# SCH_Instruction_Register_2021-10-21.net
KiCad netlist of a schematic drawn in EasyEDA
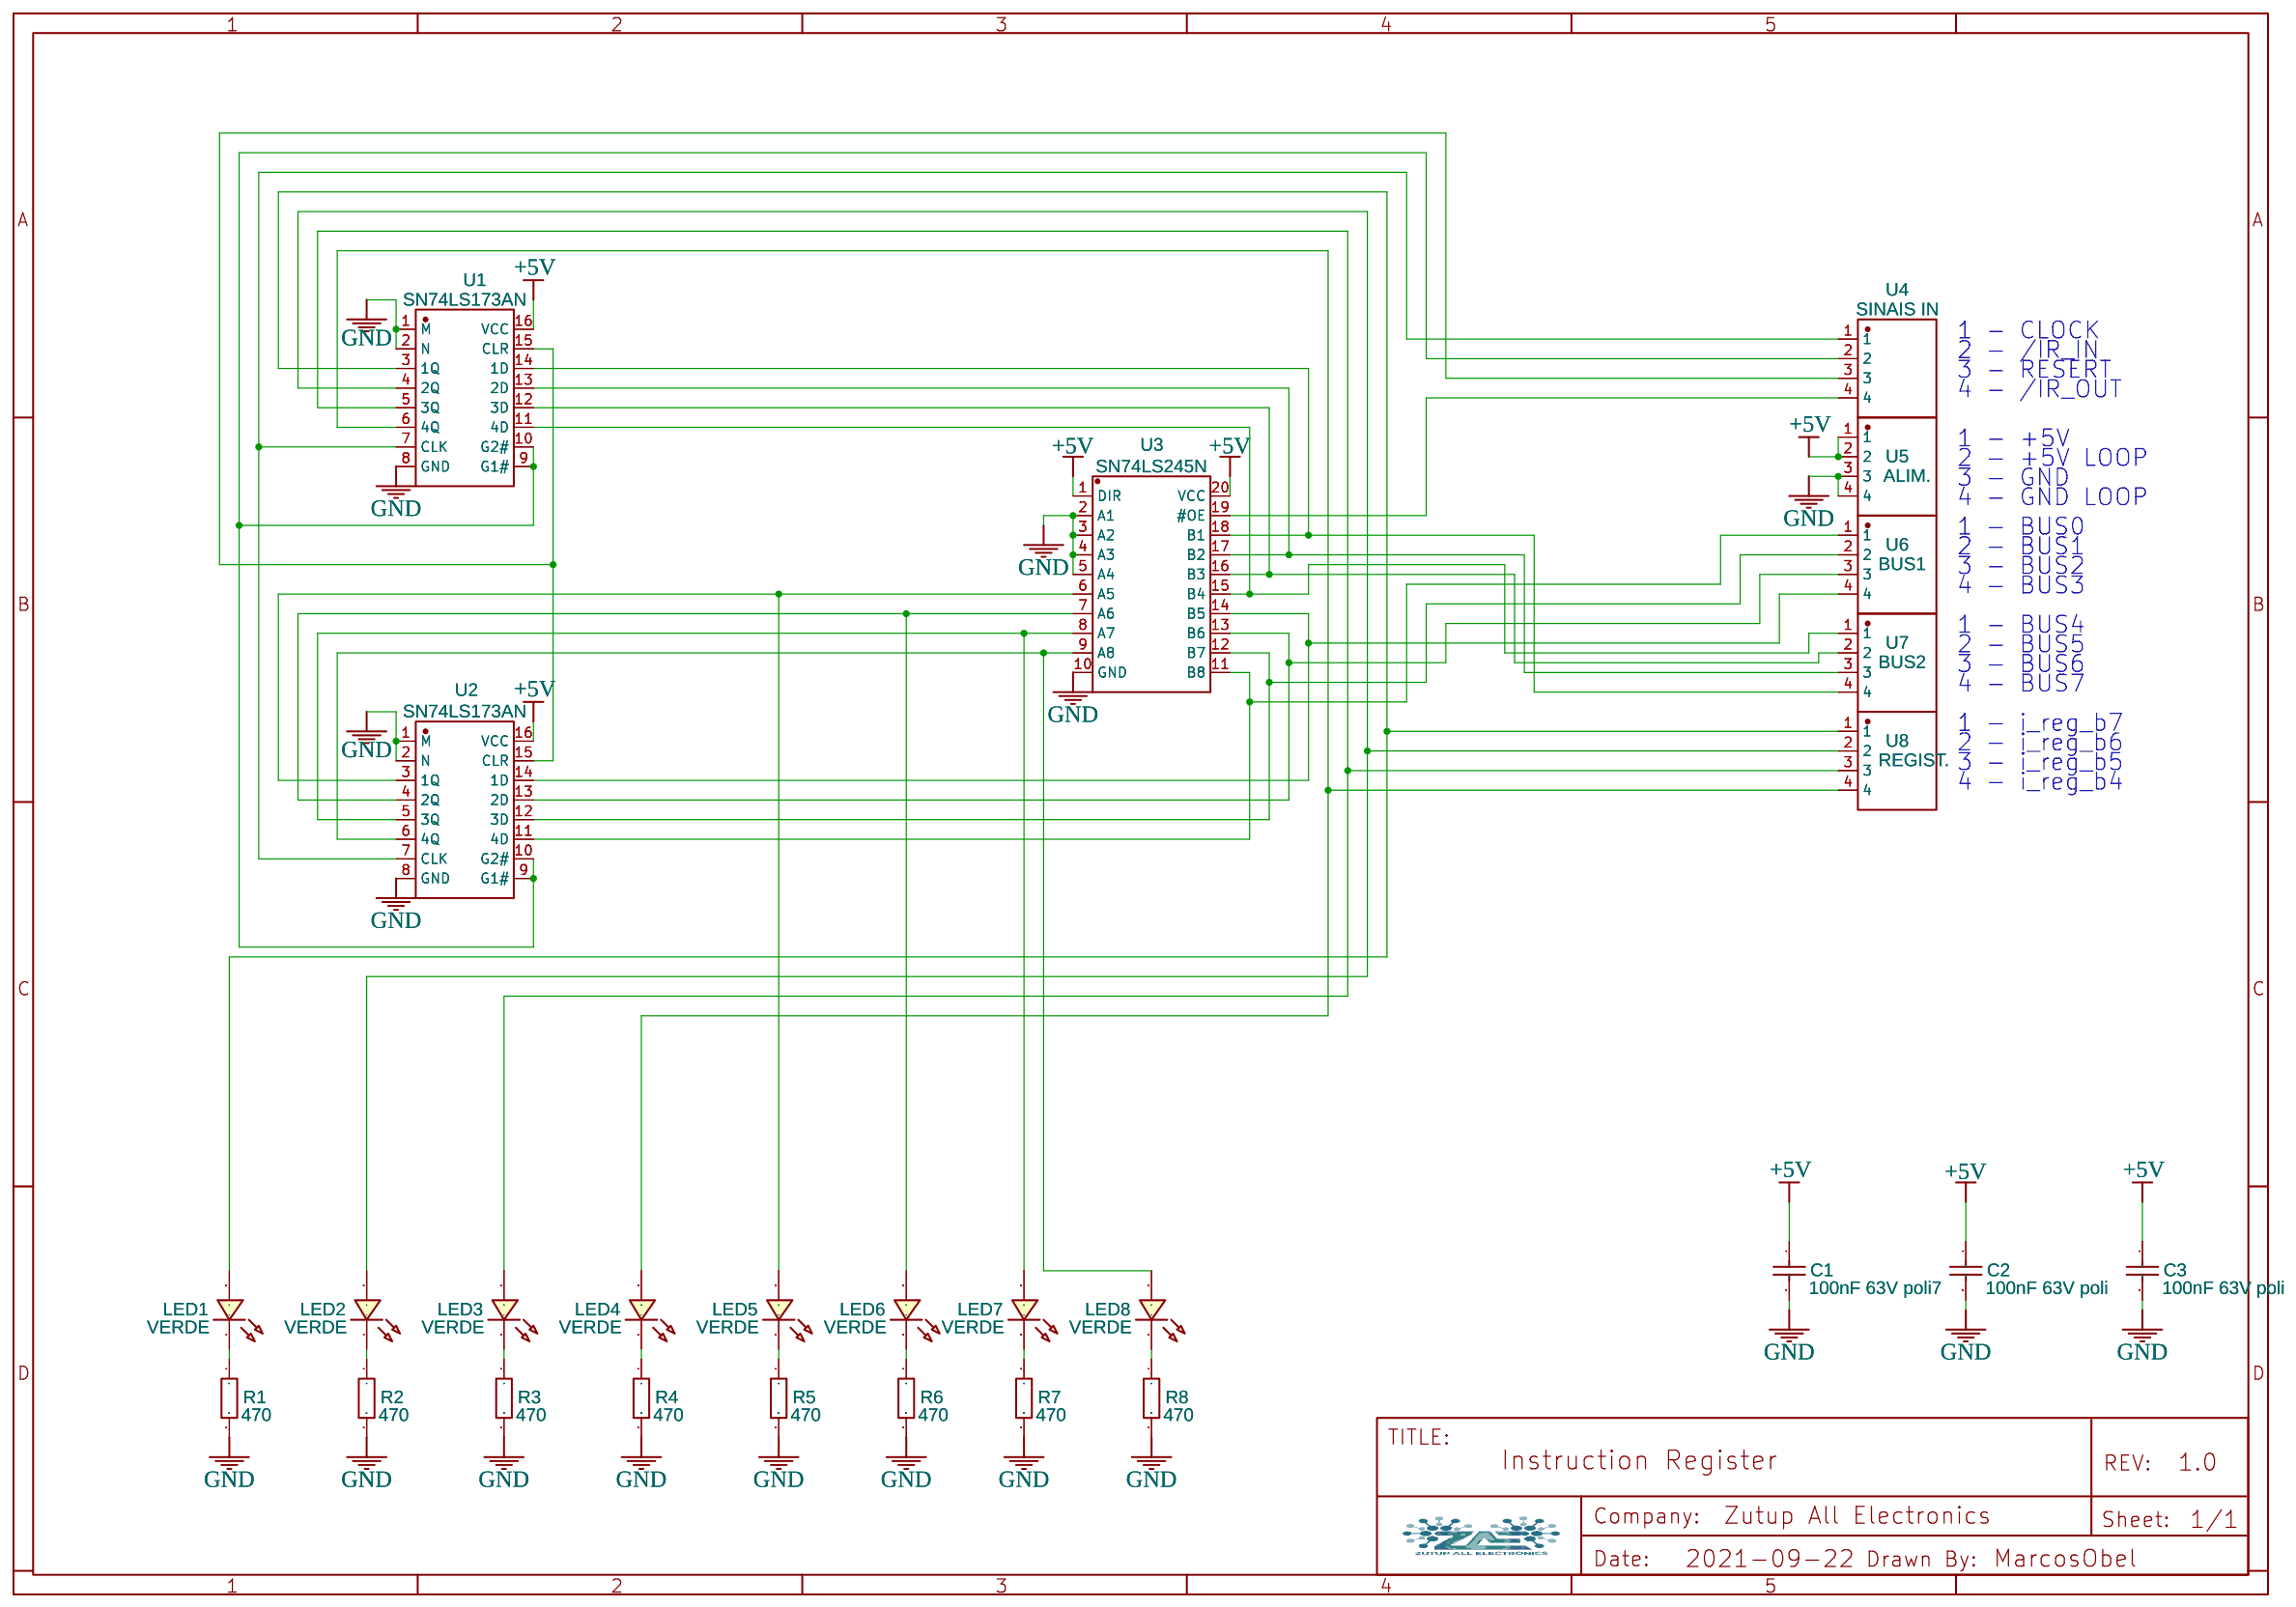
[diagram p0: schematic sheet]

(export (version "E")
  (design (tool "Eeschema 10.0.6"))
  (components
    (comp (ref "C1")
      (value "100nF 63V poli7")
      (fields
        (field (name "BOM_Manufacturer Part") "SR305C105KAR")
        (field (name "BOM_Supplier Part") "C444741")
      )
      (libsource (lib "") (part "SR305C105KAR"))
    )
    (comp (ref "C2")
      (value "100nF 63V poli")
      (fields
        (field (name "BOM_Manufacturer Part") "SR305C105KAR")
        (field (name "BOM_Supplier Part") "C444741")
      )
      (libsource (lib "") (part "SR305C105KAR"))
    )
    (comp (ref "C3")
      (value "100nF 63V poli")
      (fields
        (field (name "BOM_Manufacturer Part") "SR305C105KAR")
        (field (name "BOM_Supplier Part") "C444741")
      )
      (libsource (lib "") (part "SR305C105KAR"))
    )
    (comp (ref "LED1")
      (value "VERDE")
      (fields (field (name "BOM_Manufacturer Part") "264-7GD") (field (name "BOM_Supplier Part") "C605465"))
      (libsource (lib "") (part "264-7GD"))
    )
    (comp (ref "LED2")
      (value "VERDE")
      (fields (field (name "BOM_Manufacturer Part") "264-7GD") (field (name "BOM_Supplier Part") "C605465"))
      (libsource (lib "") (part "264-7GD"))
    )
    (comp (ref "LED3")
      (value "VERDE")
      (fields (field (name "BOM_Manufacturer Part") "264-7GD") (field (name "BOM_Supplier Part") "C605465"))
      (libsource (lib "") (part "264-7GD"))
    )
    (comp (ref "LED4")
      (value "VERDE")
      (fields (field (name "BOM_Manufacturer Part") "264-7GD") (field (name "BOM_Supplier Part") "C605465"))
      (libsource (lib "") (part "264-7GD"))
    )
    (comp (ref "LED5")
      (value "VERDE")
      (fields (field (name "BOM_Manufacturer Part") "264-7GD") (field (name "BOM_Supplier Part") "C605465"))
      (libsource (lib "") (part "264-7GD"))
    )
    (comp (ref "LED6")
      (value "VERDE")
      (fields (field (name "BOM_Manufacturer Part") "264-7GD") (field (name "BOM_Supplier Part") "C605465"))
      (libsource (lib "") (part "264-7GD"))
    )
    (comp (ref "LED7")
      (value "VERDE")
      (fields (field (name "BOM_Manufacturer Part") "264-7GD") (field (name "BOM_Supplier Part") "C605465"))
      (libsource (lib "") (part "264-7GD"))
    )
    (comp (ref "LED8")
      (value "VERDE")
      (fields (field (name "BOM_Manufacturer Part") "264-7GD") (field (name "BOM_Supplier Part") "C605465"))
      (libsource (lib "") (part "264-7GD"))
    )
    (comp (ref "R1")
      (value "470")
      (fields
        (field (name "BOM_Manufacturer Part") "CFR02SJ0823A10")
        (field (name "BOM_Supplier Part") "C69876")
      )
      (libsource (lib "") (part "CFR02SJ0823A10"))
    )
    (comp (ref "R2")
      (value "470")
      (fields
        (field (name "BOM_Manufacturer Part") "CFR02SJ0823A10")
        (field (name "BOM_Supplier Part") "C69876")
      )
      (libsource (lib "") (part "CFR02SJ0823A10"))
    )
    (comp (ref "R3")
      (value "470")
      (fields
        (field (name "BOM_Manufacturer Part") "CFR02SJ0823A10")
        (field (name "BOM_Supplier Part") "C69876")
      )
      (libsource (lib "") (part "CFR02SJ0823A10"))
    )
    (comp (ref "R4")
      (value "470")
      (fields
        (field (name "BOM_Manufacturer Part") "CFR02SJ0823A10")
        (field (name "BOM_Supplier Part") "C69876")
      )
      (libsource (lib "") (part "CFR02SJ0823A10"))
    )
    (comp (ref "R5")
      (value "470")
      (fields
        (field (name "BOM_Manufacturer Part") "CFR02SJ0823A10")
        (field (name "BOM_Supplier Part") "C69876")
      )
      (libsource (lib "") (part "CFR02SJ0823A10"))
    )
    (comp (ref "R6")
      (value "470")
      (fields
        (field (name "BOM_Manufacturer Part") "CFR02SJ0823A10")
        (field (name "BOM_Supplier Part") "C69876")
      )
      (libsource (lib "") (part "CFR02SJ0823A10"))
    )
    (comp (ref "R7")
      (value "470")
      (fields
        (field (name "BOM_Manufacturer Part") "CFR02SJ0823A10")
        (field (name "BOM_Supplier Part") "C69876")
      )
      (libsource (lib "") (part "CFR02SJ0823A10"))
    )
    (comp (ref "R8")
      (value "470")
      (fields
        (field (name "BOM_Manufacturer Part") "CFR02SJ0823A10")
        (field (name "BOM_Supplier Part") "C69876")
      )
      (libsource (lib "") (part "CFR02SJ0823A10"))
    )
    (comp (ref "U1")
      (value "SN74LS173AN")
      (fields (field (name "BOM_Supplier Part") "C1550125"))
      (libsource (lib "") (part "SN74LS173AN"))
    )
    (comp (ref "U2")
      (value "SN74LS173AN")
      (fields (field (name "BOM_Supplier Part") "C1550125"))
      (libsource (lib "") (part "SN74LS173AN"))
    )
    (comp (ref "U3")
      (value "SN74LS245N")
      (fields (field (name "BOM_Supplier Part") "C352966"))
      (libsource (lib "") (part "SN74LS245N"))
    )
    (comp (ref "U4")
      (value "SINAIS IN")
      (fields (field (name "BOM_Manufacturer Part") "171825-4") (field (name "BOM_Supplier Part") "C210162"))
      (libsource (lib "") (part "171825-4"))
    )
    (comp (ref "U5")
      (value "ALIM.")
      (fields (field (name "BOM_Manufacturer Part") "171825-4") (field (name "BOM_Supplier Part") "C210162"))
      (libsource (lib "") (part "171825-4"))
    )
    (comp (ref "U6")
      (value "BUS1")
      (fields (field (name "BOM_Manufacturer Part") "171825-4") (field (name "BOM_Supplier Part") "C210162"))
      (libsource (lib "") (part "171825-4"))
    )
    (comp (ref "U7")
      (value "BUS2")
      (fields (field (name "BOM_Manufacturer Part") "171825-4") (field (name "BOM_Supplier Part") "C210162"))
      (libsource (lib "") (part "171825-4"))
    )
    (comp (ref "U8")
      (value "REGIST.")
      (fields (field (name "BOM_Manufacturer Part") "171825-4") (field (name "BOM_Supplier Part") "C210162"))
      (libsource (lib "") (part "171825-4"))
    )
  )
  (nets
    (net (code "1") (name "+5V") (class "Default")
      (node (ref "C1") (pin "1") (pinfunction "1_1") (pintype "input"))
      (node (ref "C2") (pin "1") (pinfunction "1_1") (pintype "input"))
      (node (ref "C3") (pin "1") (pinfunction "1_1") (pintype "input"))
      (node (ref "U1") (pin "16") (pinfunction "VCC_16") (pintype "unspecified"))
      (node (ref "U2") (pin "16") (pinfunction "VCC_16") (pintype "unspecified"))
      (node (ref "U3") (pin "1") (pinfunction "DIR_1") (pintype "unspecified"))
      (node (ref "U3") (pin "20") (pinfunction "VCC_20") (pintype "unspecified"))
      (node (ref "U5") (pin "1") (pinfunction "1_1") (pintype "unspecified"))
      (node (ref "U5") (pin "2") (pinfunction "2_2") (pintype "unspecified"))
    )
    (net (code "2") (name "GND") (class "Default")
      (node (ref "C1") (pin "2") (pinfunction "2_2") (pintype "input"))
      (node (ref "C2") (pin "2") (pinfunction "2_2") (pintype "input"))
      (node (ref "C3") (pin "2") (pinfunction "2_2") (pintype "input"))
      (node (ref "R1") (pin "2") (pinfunction "2_2") (pintype "input"))
      (node (ref "R2") (pin "2") (pinfunction "2_2") (pintype "input"))
      (node (ref "R3") (pin "2") (pinfunction "2_2") (pintype "input"))
      (node (ref "R4") (pin "2") (pinfunction "2_2") (pintype "input"))
      (node (ref "R5") (pin "2") (pinfunction "2_2") (pintype "input"))
      (node (ref "R6") (pin "2") (pinfunction "2_2") (pintype "input"))
      (node (ref "R7") (pin "2") (pinfunction "2_2") (pintype "input"))
      (node (ref "R8") (pin "2") (pinfunction "2_2") (pintype "input"))
      (node (ref "U1") (pin "1") (pinfunction "M_1") (pintype "unspecified"))
      (node (ref "U1") (pin "2") (pinfunction "N_2") (pintype "unspecified"))
      (node (ref "U1") (pin "8") (pinfunction "GND_8") (pintype "unspecified"))
      (node (ref "U2") (pin "1") (pinfunction "M_1") (pintype "unspecified"))
      (node (ref "U2") (pin "2") (pinfunction "N_2") (pintype "unspecified"))
      (node (ref "U2") (pin "8") (pinfunction "GND_8") (pintype "unspecified"))
      (node (ref "U3") (pin "10") (pinfunction "GND_10") (pintype "unspecified"))
      (node (ref "U3") (pin "2") (pinfunction "A1_2") (pintype "unspecified"))
      (node (ref "U3") (pin "3") (pinfunction "A2_3") (pintype "unspecified"))
      (node (ref "U3") (pin "4") (pinfunction "A3_4") (pintype "unspecified"))
      (node (ref "U3") (pin "5") (pinfunction "A4_5") (pintype "unspecified"))
      (node (ref "U5") (pin "3") (pinfunction "3_3") (pintype "unspecified"))
      (node (ref "U5") (pin "4") (pinfunction "4_4") (pintype "unspecified"))
    )
    (net (code "3") (name "Net-(LED1-+)") (class "Default")
      (node (ref "LED1") (pin "2") (pinfunction "+_2") (pintype "unspecified"))
      (node (ref "U1") (pin "3") (pinfunction "1Q_3") (pintype "unspecified"))
      (node (ref "U8") (pin "1") (pinfunction "1_1") (pintype "unspecified"))
    )
    (net (code "4") (name "Net-(LED1--)") (class "Default")
      (node (ref "LED1") (pin "1") (pinfunction "-_1") (pintype "unspecified"))
      (node (ref "R1") (pin "1") (pinfunction "1_1") (pintype "input"))
    )
    (net (code "5") (name "Net-(LED2-+)") (class "Default")
      (node (ref "LED2") (pin "2") (pinfunction "+_2") (pintype "unspecified"))
      (node (ref "U1") (pin "4") (pinfunction "2Q_4") (pintype "unspecified"))
      (node (ref "U8") (pin "2") (pinfunction "2_2") (pintype "unspecified"))
    )
    (net (code "6") (name "Net-(LED2--)") (class "Default")
      (node (ref "LED2") (pin "1") (pinfunction "-_1") (pintype "unspecified"))
      (node (ref "R2") (pin "1") (pinfunction "1_1") (pintype "input"))
    )
    (net (code "7") (name "Net-(LED3-+)") (class "Default")
      (node (ref "LED3") (pin "2") (pinfunction "+_2") (pintype "unspecified"))
      (node (ref "U1") (pin "5") (pinfunction "3Q_5") (pintype "unspecified"))
      (node (ref "U8") (pin "3") (pinfunction "3_3") (pintype "unspecified"))
    )
    (net (code "8") (name "Net-(LED3--)") (class "Default")
      (node (ref "LED3") (pin "1") (pinfunction "-_1") (pintype "unspecified"))
      (node (ref "R3") (pin "1") (pinfunction "1_1") (pintype "input"))
    )
    (net (code "9") (name "Net-(LED4-+)") (class "Default")
      (node (ref "LED4") (pin "2") (pinfunction "+_2") (pintype "unspecified"))
      (node (ref "U1") (pin "6") (pinfunction "4Q_6") (pintype "unspecified"))
      (node (ref "U8") (pin "4") (pinfunction "4_4") (pintype "unspecified"))
    )
    (net (code "10") (name "Net-(LED4--)") (class "Default")
      (node (ref "LED4") (pin "1") (pinfunction "-_1") (pintype "unspecified"))
      (node (ref "R4") (pin "1") (pinfunction "1_1") (pintype "input"))
    )
    (net (code "11") (name "Net-(LED5-+)") (class "Default")
      (node (ref "LED5") (pin "2") (pinfunction "+_2") (pintype "unspecified"))
      (node (ref "U2") (pin "3") (pinfunction "1Q_3") (pintype "unspecified"))
      (node (ref "U3") (pin "6") (pinfunction "A5_6") (pintype "unspecified"))
    )
    (net (code "12") (name "Net-(LED5--)") (class "Default")
      (node (ref "LED5") (pin "1") (pinfunction "-_1") (pintype "unspecified"))
      (node (ref "R5") (pin "1") (pinfunction "1_1") (pintype "input"))
    )
    (net (code "13") (name "Net-(LED6-+)") (class "Default")
      (node (ref "LED6") (pin "2") (pinfunction "+_2") (pintype "unspecified"))
      (node (ref "U2") (pin "4") (pinfunction "2Q_4") (pintype "unspecified"))
      (node (ref "U3") (pin "7") (pinfunction "A6_7") (pintype "unspecified"))
    )
    (net (code "14") (name "Net-(LED6--)") (class "Default")
      (node (ref "LED6") (pin "1") (pinfunction "-_1") (pintype "unspecified"))
      (node (ref "R6") (pin "1") (pinfunction "1_1") (pintype "input"))
    )
    (net (code "15") (name "Net-(LED7-+)") (class "Default")
      (node (ref "LED7") (pin "2") (pinfunction "+_2") (pintype "unspecified"))
      (node (ref "U2") (pin "5") (pinfunction "3Q_5") (pintype "unspecified"))
      (node (ref "U3") (pin "8") (pinfunction "A7_8") (pintype "unspecified"))
    )
    (net (code "16") (name "Net-(LED7--)") (class "Default")
      (node (ref "LED7") (pin "1") (pinfunction "-_1") (pintype "unspecified"))
      (node (ref "R7") (pin "1") (pinfunction "1_1") (pintype "input"))
    )
    (net (code "17") (name "Net-(LED8-+)") (class "Default")
      (node (ref "LED8") (pin "2") (pinfunction "+_2") (pintype "unspecified"))
      (node (ref "U2") (pin "6") (pinfunction "4Q_6") (pintype "unspecified"))
      (node (ref "U3") (pin "9") (pinfunction "A8_9") (pintype "unspecified"))
    )
    (net (code "18") (name "Net-(LED8--)") (class "Default")
      (node (ref "LED8") (pin "1") (pinfunction "-_1") (pintype "unspecified"))
      (node (ref "R8") (pin "1") (pinfunction "1_1") (pintype "input"))
    )
    (net (code "19") (name "Net-(U1-1D)") (class "Default")
      (node (ref "U1") (pin "14") (pinfunction "1D_14") (pintype "unspecified"))
      (node (ref "U3") (pin "18") (pinfunction "B1_18") (pintype "unspecified"))
      (node (ref "U7") (pin "4") (pinfunction "4_4") (pintype "unspecified"))
    )
    (net (code "20") (name "Net-(U1-2D)") (class "Default")
      (node (ref "U1") (pin "13") (pinfunction "2D_13") (pintype "unspecified"))
      (node (ref "U3") (pin "17") (pinfunction "B2_17") (pintype "unspecified"))
      (node (ref "U7") (pin "3") (pinfunction "3_3") (pintype "unspecified"))
    )
    (net (code "21") (name "Net-(U1-3D)") (class "Default")
      (node (ref "U1") (pin "12") (pinfunction "3D_12") (pintype "unspecified"))
      (node (ref "U3") (pin "16") (pinfunction "B3_16") (pintype "unspecified"))
      (node (ref "U7") (pin "2") (pinfunction "2_2") (pintype "unspecified"))
    )
    (net (code "22") (name "Net-(U1-4D)") (class "Default")
      (node (ref "U1") (pin "11") (pinfunction "4D_11") (pintype "unspecified"))
      (node (ref "U3") (pin "15") (pinfunction "B4_15") (pintype "unspecified"))
      (node (ref "U7") (pin "1") (pinfunction "1_1") (pintype "unspecified"))
    )
    (net (code "23") (name "Net-(U1-CLK)") (class "Default")
      (node (ref "U1") (pin "7") (pinfunction "CLK_7") (pintype "unspecified"))
      (node (ref "U2") (pin "7") (pinfunction "CLK_7") (pintype "unspecified"))
      (node (ref "U4") (pin "1") (pinfunction "1_1") (pintype "unspecified"))
    )
    (net (code "24") (name "Net-(U1-CLR)") (class "Default")
      (node (ref "U1") (pin "15") (pinfunction "CLR_15") (pintype "unspecified"))
      (node (ref "U2") (pin "15") (pinfunction "CLR_15") (pintype "unspecified"))
      (node (ref "U4") (pin "3") (pinfunction "3_3") (pintype "unspecified"))
    )
    (net (code "25") (name "Net-(U1-G1#)") (class "Default")
      (node (ref "U1") (pin "10") (pinfunction "G2#_10") (pintype "unspecified"))
      (node (ref "U1") (pin "9") (pinfunction "G1#_9") (pintype "unspecified"))
      (node (ref "U2") (pin "10") (pinfunction "G2#_10") (pintype "unspecified"))
      (node (ref "U2") (pin "9") (pinfunction "G1#_9") (pintype "unspecified"))
      (node (ref "U4") (pin "2") (pinfunction "2_2") (pintype "unspecified"))
    )
    (net (code "26") (name "Net-(U2-1D)") (class "Default")
      (node (ref "U2") (pin "14") (pinfunction "1D_14") (pintype "unspecified"))
      (node (ref "U3") (pin "14") (pinfunction "B5_14") (pintype "unspecified"))
      (node (ref "U6") (pin "4") (pinfunction "4_4") (pintype "unspecified"))
    )
    (net (code "27") (name "Net-(U2-2D)") (class "Default")
      (node (ref "U2") (pin "13") (pinfunction "2D_13") (pintype "unspecified"))
      (node (ref "U3") (pin "13") (pinfunction "B6_13") (pintype "unspecified"))
      (node (ref "U6") (pin "3") (pinfunction "3_3") (pintype "unspecified"))
    )
    (net (code "28") (name "Net-(U2-3D)") (class "Default")
      (node (ref "U2") (pin "12") (pinfunction "3D_12") (pintype "unspecified"))
      (node (ref "U3") (pin "12") (pinfunction "B7_12") (pintype "unspecified"))
      (node (ref "U6") (pin "2") (pinfunction "2_2") (pintype "unspecified"))
    )
    (net (code "29") (name "Net-(U2-4D)") (class "Default")
      (node (ref "U2") (pin "11") (pinfunction "4D_11") (pintype "unspecified"))
      (node (ref "U3") (pin "11") (pinfunction "B8_11") (pintype "unspecified"))
      (node (ref "U6") (pin "1") (pinfunction "1_1") (pintype "unspecified"))
    )
    (net (code "30") (name "Net-(U3-#OE)") (class "Default")
      (node (ref "U3") (pin "19") (pinfunction "#OE_19") (pintype "unspecified"))
      (node (ref "U4") (pin "4") (pinfunction "4_4") (pintype "unspecified"))
    )
  )
)
